# AutomaticBacklight.net
KiCad netlist of a schematic drawn in Altium Designer
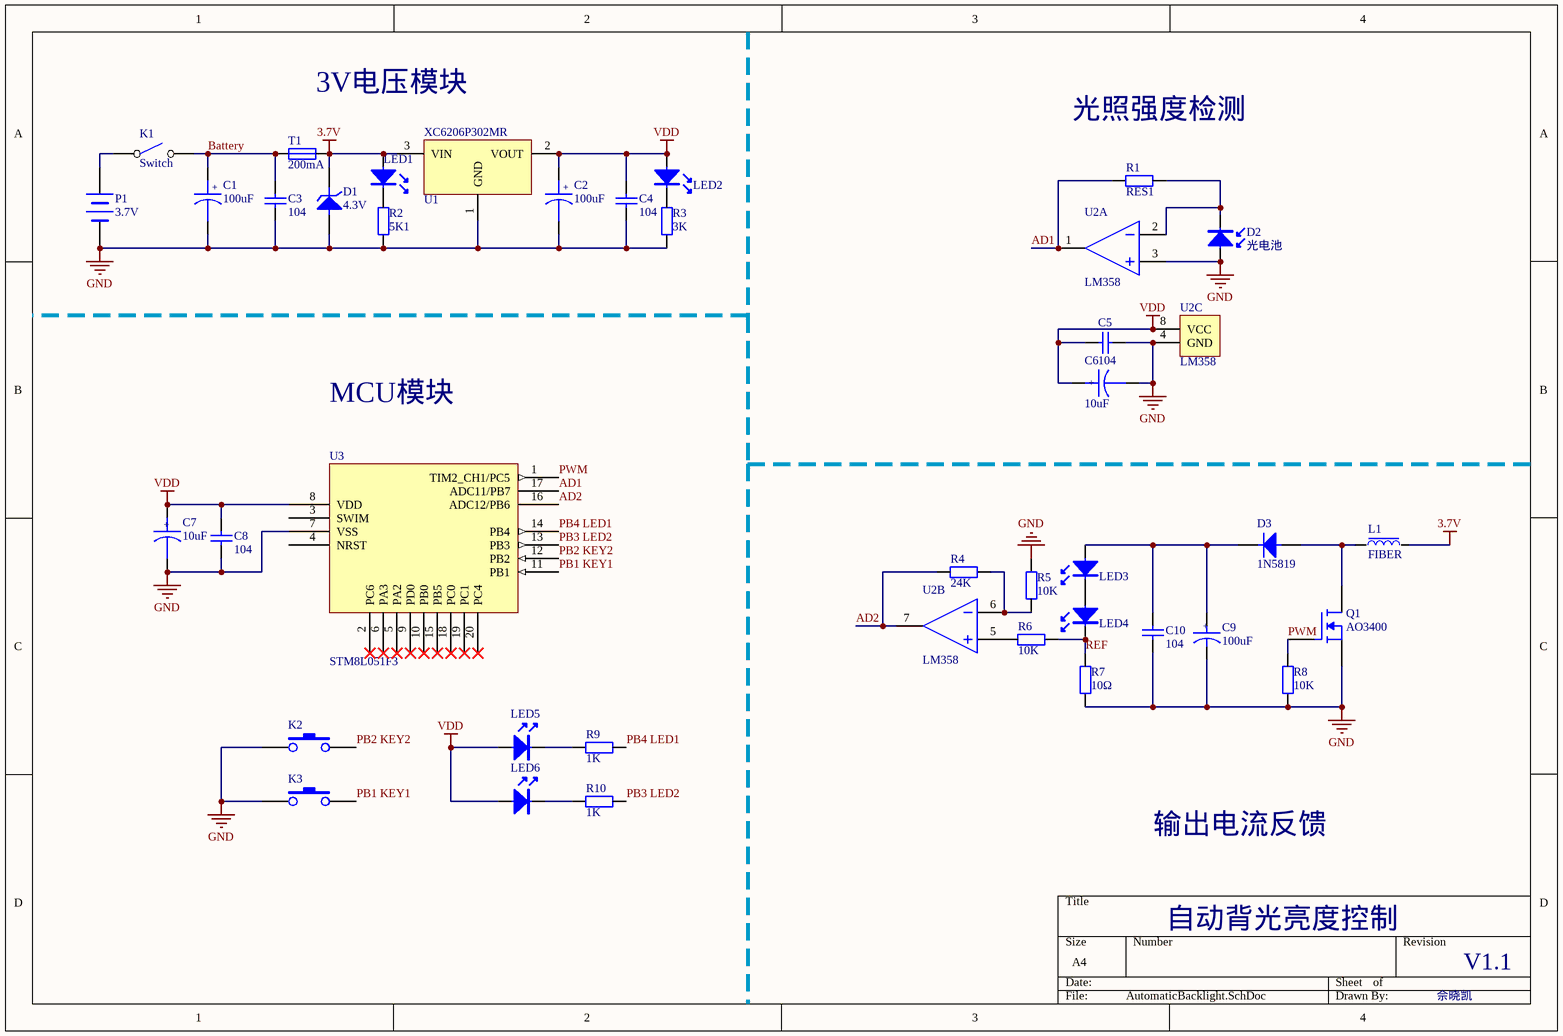
[diagram p0: AutomaticBacklight.SchDoc]

(export (version "E")
  (design (tool "Eeschema 10.0.6"))
  (components
    (comp (ref "C1") (value "100uF") (description "电解电容") (libsource (lib "") (part "Cap2_1")))
    (comp (ref "C2") (value "100uF") (description "电解电容") (libsource (lib "") (part "Cap2_1")))
    (comp (ref "C3")
      (value "104")
      (footprint "0805C")
      (description "无极性电容")
      (libsource (lib "常用元器件库") (part "Cap1"))
    )
    (comp (ref "C4")
      (value "104")
      (footprint "0805C")
      (description "无极性电容")
      (libsource (lib "常用元器件库") (part "Cap1"))
    )
    (comp (ref "C5")
      (value "104")
      (footprint "0805C")
      (description "无极性电容")
      (libsource (lib "常用元器件库") (part "Cap1"))
    )
    (comp (ref "C6") (value "10uF") (description "电解电容") (libsource (lib "常用元器件库") (part "Cap2")))
    (comp (ref "C7") (value "10uF") (description "电解电容") (libsource (lib "常用元器件库") (part "Cap2")))
    (comp (ref "C8")
      (value "104")
      (footprint "0805C")
      (description "无极性电容")
      (libsource (lib "常用元器件库") (part "Cap1"))
    )
    (comp (ref "C9") (value "100uF") (description "电解电容") (libsource (lib "") (part "Cap2_2")))
    (comp (ref "C10")
      (value "104")
      (footprint "0805C")
      (description "无极性电容")
      (libsource (lib "常用元器件库") (part "Cap1"))
    )
    (comp (ref "D1")
      (value "4.3V")
      (description "稳压二极管")
      (libsource (lib "常用元器件库") (part "StabilivoltDiode"))
    )
    (comp (ref "D2") (value "光电池") (libsource (lib "常用元器件库") (part "LightCell")))
    (comp (ref "D3") (value "1N5819") (description "二极管") (libsource (lib "常用元器件库") (part "DIODE")))
    (comp (ref "K1")
      (value "Switch")
      (footprint "Switch1")
      (description "开关")
      (libsource (lib "常用元器件库") (part "Switch"))
    )
    (comp (ref "K2") (value "Botton") (libsource (lib "常用元器件库") (part "Botton")))
    (comp (ref "K3") (value "Botton") (libsource (lib "常用元器件库") (part "Botton")))
    (comp (ref "L1") (value "FIBER") (libsource (lib "AutomaticBacklight") (part "FIBER")))
    (comp (ref "LED1") (value "LED") (libsource (lib "常用元器件库") (part "LED")))
    (comp (ref "LED2") (value "LED") (libsource (lib "常用元器件库") (part "LED")))
    (comp (ref "LED3") (value "LED") (libsource (lib "常用元器件库") (part "LED")))
    (comp (ref "LED4") (value "LED") (libsource (lib "常用元器件库") (part "LED")))
    (comp (ref "LED5") (value "LED") (libsource (lib "常用元器件库") (part "LED")))
    (comp (ref "LED6") (value "LED") (libsource (lib "常用元器件库") (part "LED")))
    (comp (ref "P1") (value "3.7V") (description "电池") (libsource (lib "常用元器件库") (part "Battery")))
    (comp (ref "Q1") (value "AO3400") (libsource (lib "常用元器件库") (part "NMOS(增强型)")))
    (comp (ref "R1") (value "RES1") (libsource (lib "") (part "RES1_2")))
    (comp (ref "R2") (value "5K1") (libsource (lib "") (part "RES1_2")))
    (comp (ref "R3") (value "3K") (libsource (lib "") (part "RES1_2")))
    (comp (ref "R4") (value "24K") (libsource (lib "") (part "RES1_1")))
    (comp (ref "R5") (value "10K") (libsource (lib "") (part "RES1_3")))
    (comp (ref "R6") (value "10K") (libsource (lib "") (part "RES1_1")))
    (comp (ref "R7") (value "10Ω") (libsource (lib "常用元器件库") (part "RES1")))
    (comp (ref "R8") (value "10K") (libsource (lib "常用元器件库") (part "RES1")))
    (comp (ref "R9") (value "1K") (libsource (lib "常用元器件库") (part "RES1")))
    (comp (ref "R10") (value "1K") (libsource (lib "常用元器件库") (part "RES1")))
    (comp (ref "T1") (value "200mA") (description "保险管") (libsource (lib "常用元器件库") (part "InsurancePipe")))
    (comp (ref "U1") (value "XC6206P302MR") (description "SOT-23封装") (libsource (lib "电源芯片") (part "XC6206")))
    (comp (ref "U2") (value "LM358") (description "运算放大器") (libsource (lib "运算放大器") (part "LM358")))
    (comp (ref "U3") (value "STM8L051F3") (libsource (lib "AutomaticBacklight") (part "STM8L051F3")))
  )
  (nets
    (net (code "1") (name "/AD1") (class "Default")
      (node (ref "R1") (pin "1") (pinfunction "1_1") (pintype "passive"))
      (node (ref "U2") (pin "1") (pinfunction "OUT_1") (pintype "passive"))
      (node (ref "U3") (pin "17") (pinfunction "ADC11/PB7_17") (pintype "tri_state"))
    )
    (net (code "2") (name "/AD2") (class "Default")
      (node (ref "R4") (pin "2") (pinfunction "2_2") (pintype "passive"))
      (node (ref "U2") (pin "7") (pinfunction "OUT_7") (pintype "passive"))
      (node (ref "U3") (pin "16") (pinfunction "ADC12/PB6_16") (pintype "tri_state"))
    )
    (net (code "3") (name "/Battery") (class "Default")
      (node (ref "C1") (pin "A") (pinfunction "1_A") (pintype "passive"))
      (node (ref "C3") (pin "2") (pinfunction "2_2") (pintype "passive"))
      (node (ref "K1") (pin "2") (pinfunction "2_2") (pintype "passive"))
      (node (ref "T1") (pin "1") (pinfunction "1_1") (pintype "passive"))
    )
    (net (code "4") (name "/PB1 KEY1") (class "Default")
      (node (ref "K3") (pin "2") (pinfunction "2_2") (pintype "passive"))
      (node (ref "U3") (pin "11") (pinfunction "PB1_11") (pintype "input"))
    )
    (net (code "5") (name "/PB2 KEY2") (class "Default")
      (node (ref "K2") (pin "2") (pinfunction "2_2") (pintype "passive"))
      (node (ref "U3") (pin "12") (pinfunction "PB2_12") (pintype "input"))
    )
    (net (code "6") (name "/PB3 LED2") (class "Default")
      (node (ref "R10") (pin "2") (pinfunction "2_2") (pintype "passive"))
      (node (ref "U3") (pin "13") (pinfunction "PB3_13") (pintype "output"))
    )
    (net (code "7") (name "/PB4 LED1") (class "Default")
      (node (ref "R9") (pin "2") (pinfunction "2_2") (pintype "passive"))
      (node (ref "U3") (pin "14") (pinfunction "PB4_14") (pintype "output"))
    )
    (net (code "8") (name "/PWM") (class "Default")
      (node (ref "Q1") (pin "1") (pinfunction "G_1") (pintype "passive"))
      (node (ref "R8") (pin "2") (pinfunction "2_2") (pintype "passive"))
      (node (ref "U3") (pin "1") (pinfunction "TIM2_CH1/PC5_1") (pintype "output"))
    )
    (net (code "9") (name "/REF") (class "Default")
      (node (ref "LED4") (pin "K") (pinfunction "2_K") (pintype "passive"))
      (node (ref "R6") (pin "1") (pinfunction "1_1") (pintype "passive"))
      (node (ref "R7") (pin "2") (pinfunction "2_2") (pintype "passive"))
    )
    (net (code "10") (name "3.7V") (class "Default")
      (node (ref "D1") (pin "K") (pinfunction "K_K") (pintype "passive"))
      (node (ref "L1") (pin "1") (pintype "passive"))
      (node (ref "LED1") (pin "A") (pinfunction "1_A") (pintype "passive"))
      (node (ref "T1") (pin "2") (pinfunction "2_2") (pintype "passive"))
      (node (ref "U1") (pin "3") (pinfunction "VIN_3") (pintype "power_in"))
    )
    (net (code "11") (name "GND") (class "Default")
      (node (ref "C1") (pin "K") (pinfunction "2_K") (pintype "passive"))
      (node (ref "C10") (pin "2") (pinfunction "2_2") (pintype "passive"))
      (node (ref "C2") (pin "K") (pinfunction "2_K") (pintype "passive"))
      (node (ref "C3") (pin "1") (pinfunction "1_1") (pintype "passive"))
      (node (ref "C4") (pin "2") (pinfunction "2_2") (pintype "passive"))
      (node (ref "C5") (pin "2") (pinfunction "2_2") (pintype "passive"))
      (node (ref "C6") (pin "K") (pinfunction "2_K") (pintype "passive"))
      (node (ref "C7") (pin "K") (pinfunction "2_K") (pintype "passive"))
      (node (ref "C8") (pin "2") (pinfunction "2_2") (pintype "passive"))
      (node (ref "C9") (pin "K") (pinfunction "2_K") (pintype "passive"))
      (node (ref "D1") (pin "A") (pinfunction "A_A") (pintype "passive"))
      (node (ref "D2") (pin "A") (pinfunction "1_A") (pintype "passive"))
      (node (ref "K2") (pin "1") (pinfunction "1_1") (pintype "passive"))
      (node (ref "K3") (pin "1") (pinfunction "1_1") (pintype "passive"))
      (node (ref "P1") (pin "2") (pinfunction "-_2") (pintype "passive"))
      (node (ref "Q1") (pin "3") (pinfunction "S_3") (pintype "passive"))
      (node (ref "R2") (pin "1") (pinfunction "1_1") (pintype "passive"))
      (node (ref "R3") (pin "1") (pinfunction "1_1") (pintype "passive"))
      (node (ref "R5") (pin "1") (pinfunction "1_1") (pintype "passive"))
      (node (ref "R7") (pin "1") (pinfunction "1_1") (pintype "passive"))
      (node (ref "R8") (pin "1") (pinfunction "1_1") (pintype "passive"))
      (node (ref "U1") (pin "1") (pinfunction "GND_1") (pintype "power_in"))
      (node (ref "U2") (pin "3") (pinfunction "IN+_3") (pintype "passive"))
      (node (ref "U2") (pin "4") (pinfunction "GND_4") (pintype "power_in"))
      (node (ref "U3") (pin "7") (pinfunction "VSS_7") (pintype "power_in"))
    )
    (net (code "12") (name "Net-(C9-1)") (class "Default")
      (node (ref "C10") (pin "1") (pinfunction "1_1") (pintype "passive"))
      (node (ref "C9") (pin "A") (pinfunction "1_A") (pintype "passive"))
      (node (ref "D3") (pin "K") (pinfunction "K_K") (pintype "passive"))
      (node (ref "LED3") (pin "A") (pinfunction "1_A") (pintype "passive"))
    )
    (net (code "13") (name "Net-(D2-2)") (class "Default")
      (node (ref "D2") (pin "K") (pinfunction "2_K") (pintype "passive"))
      (node (ref "R1") (pin "2") (pinfunction "2_2") (pintype "passive"))
      (node (ref "U2") (pin "2") (pinfunction "IN-_2") (pintype "passive"))
    )
    (net (code "14") (name "Net-(LED3-2)") (class "Default")
      (node (ref "LED3") (pin "K") (pinfunction "2_K") (pintype "passive"))
      (node (ref "LED4") (pin "A") (pinfunction "1_A") (pintype "passive"))
    )
    (net (code "15") (name "Net-(LED5-2)") (class "Default")
      (node (ref "LED5") (pin "K") (pinfunction "2_K") (pintype "passive"))
      (node (ref "R9") (pin "1") (pinfunction "1_1") (pintype "passive"))
    )
    (net (code "16") (name "Net-(LED6-2)") (class "Default")
      (node (ref "LED6") (pin "K") (pinfunction "2_K") (pintype "passive"))
      (node (ref "R10") (pin "1") (pinfunction "1_1") (pintype "passive"))
    )
    (net (code "17") (name "Net-(P1-+)") (class "Default")
      (node (ref "K1") (pin "1") (pinfunction "1_1") (pintype "passive"))
      (node (ref "P1") (pin "1") (pinfunction "+_1") (pintype "passive"))
    )
    (net (code "18") (name "Net-(Q1-D)") (class "Default")
      (node (ref "D3") (pin "A") (pinfunction "A_A") (pintype "passive"))
      (node (ref "L1") (pin "2") (pintype "passive"))
      (node (ref "Q1") (pin "2") (pinfunction "D_2") (pintype "passive"))
    )
    (net (code "19") (name "Net-(U2B-IN+)") (class "Default")
      (node (ref "R6") (pin "2") (pinfunction "2_2") (pintype "passive"))
      (node (ref "U2") (pin "5") (pinfunction "IN+_5") (pintype "passive"))
    )
    (net (code "20") (name "Net-(U2B-IN-)") (class "Default")
      (node (ref "R4") (pin "1") (pinfunction "1_1") (pintype "passive"))
      (node (ref "R5") (pin "2") (pinfunction "2_2") (pintype "passive"))
      (node (ref "U2") (pin "6") (pinfunction "IN-_6") (pintype "passive"))
    )
    (net (code "21") (name "VDD") (class "Default")
      (node (ref "C2") (pin "A") (pinfunction "1_A") (pintype "passive"))
      (node (ref "C4") (pin "1") (pinfunction "1_1") (pintype "passive"))
      (node (ref "C5") (pin "1") (pinfunction "1_1") (pintype "passive"))
      (node (ref "C6") (pin "A") (pinfunction "1_A") (pintype "passive"))
      (node (ref "C7") (pin "A") (pinfunction "1_A") (pintype "passive"))
      (node (ref "C8") (pin "1") (pinfunction "1_1") (pintype "passive"))
      (node (ref "LED2") (pin "A") (pinfunction "1_A") (pintype "passive"))
      (node (ref "LED5") (pin "A") (pinfunction "1_A") (pintype "passive"))
      (node (ref "LED6") (pin "A") (pinfunction "1_A") (pintype "passive"))
      (node (ref "U1") (pin "2") (pinfunction "VOUT_2") (pintype "power_in"))
      (node (ref "U2") (pin "8") (pinfunction "VCC_8") (pintype "power_in"))
      (node (ref "U3") (pin "8") (pinfunction "VDD_8") (pintype "power_in"))
    )
    (net (code "22") (name "unconnected-(LED1-2-PadK)") (class "Default")
      (node (ref "LED1") (pin "K") (pinfunction "2_K") (pintype "passive"))
    )
    (net (code "23") (name "unconnected-(LED2-2-PadK)") (class "Default")
      (node (ref "LED2") (pin "K") (pinfunction "2_K") (pintype "passive"))
    )
    (net (code "24") (name "unconnected-(R2-Pad2)") (class "Default")
      (node (ref "R2") (pin "2") (pinfunction "2_2") (pintype "passive"))
    )
    (net (code "25") (name "unconnected-(R3-Pad2)") (class "Default")
      (node (ref "R3") (pin "2") (pinfunction "2_2") (pintype "passive"))
    )
    (net (code "26") (name "unconnected-(U3-NRST-Pad4)") (class "Default")
      (node (ref "U3") (pin "4") (pinfunction "NRST_4") (pintype "passive"))
    )
    (net (code "27") (name "unconnected-(U3-PA2-Pad5)") (class "Default")
      (node (ref "U3") (pin "5") (pinfunction "PA2_5") (pintype "passive+no_connect"))
    )
    (net (code "28") (name "unconnected-(U3-PA3-Pad6)") (class "Default")
      (node (ref "U3") (pin "6") (pinfunction "PA3_6") (pintype "passive+no_connect"))
    )
    (net (code "29") (name "unconnected-(U3-PB0-Pad10)") (class "Default")
      (node (ref "U3") (pin "10") (pinfunction "PB0_10") (pintype "passive+no_connect"))
    )
    (net (code "30") (name "unconnected-(U3-PB5-Pad15)") (class "Default")
      (node (ref "U3") (pin "15") (pinfunction "PB5_15") (pintype "passive+no_connect"))
    )
    (net (code "31") (name "unconnected-(U3-PC0-Pad18)") (class "Default")
      (node (ref "U3") (pin "18") (pinfunction "PC0_18") (pintype "passive+no_connect"))
    )
    (net (code "32") (name "unconnected-(U3-PC1-Pad19)") (class "Default")
      (node (ref "U3") (pin "19") (pinfunction "PC1_19") (pintype "passive+no_connect"))
    )
    (net (code "33") (name "unconnected-(U3-PC4-Pad20)") (class "Default")
      (node (ref "U3") (pin "20") (pinfunction "PC4_20") (pintype "passive+no_connect"))
    )
    (net (code "34") (name "unconnected-(U3-PC6-Pad2)") (class "Default")
      (node (ref "U3") (pin "2") (pinfunction "PC6_2") (pintype "passive+no_connect"))
    )
    (net (code "35") (name "unconnected-(U3-PD0-Pad9)") (class "Default")
      (node (ref "U3") (pin "9") (pinfunction "PD0_9") (pintype "passive+no_connect"))
    )
    (net (code "36") (name "unconnected-(U3-SWIM-Pad3)") (class "Default")
      (node (ref "U3") (pin "3") (pinfunction "SWIM_3") (pintype "passive"))
    )
  )
)
